# REC.net
KiCad netlist of a schematic drawn in Altium Designer
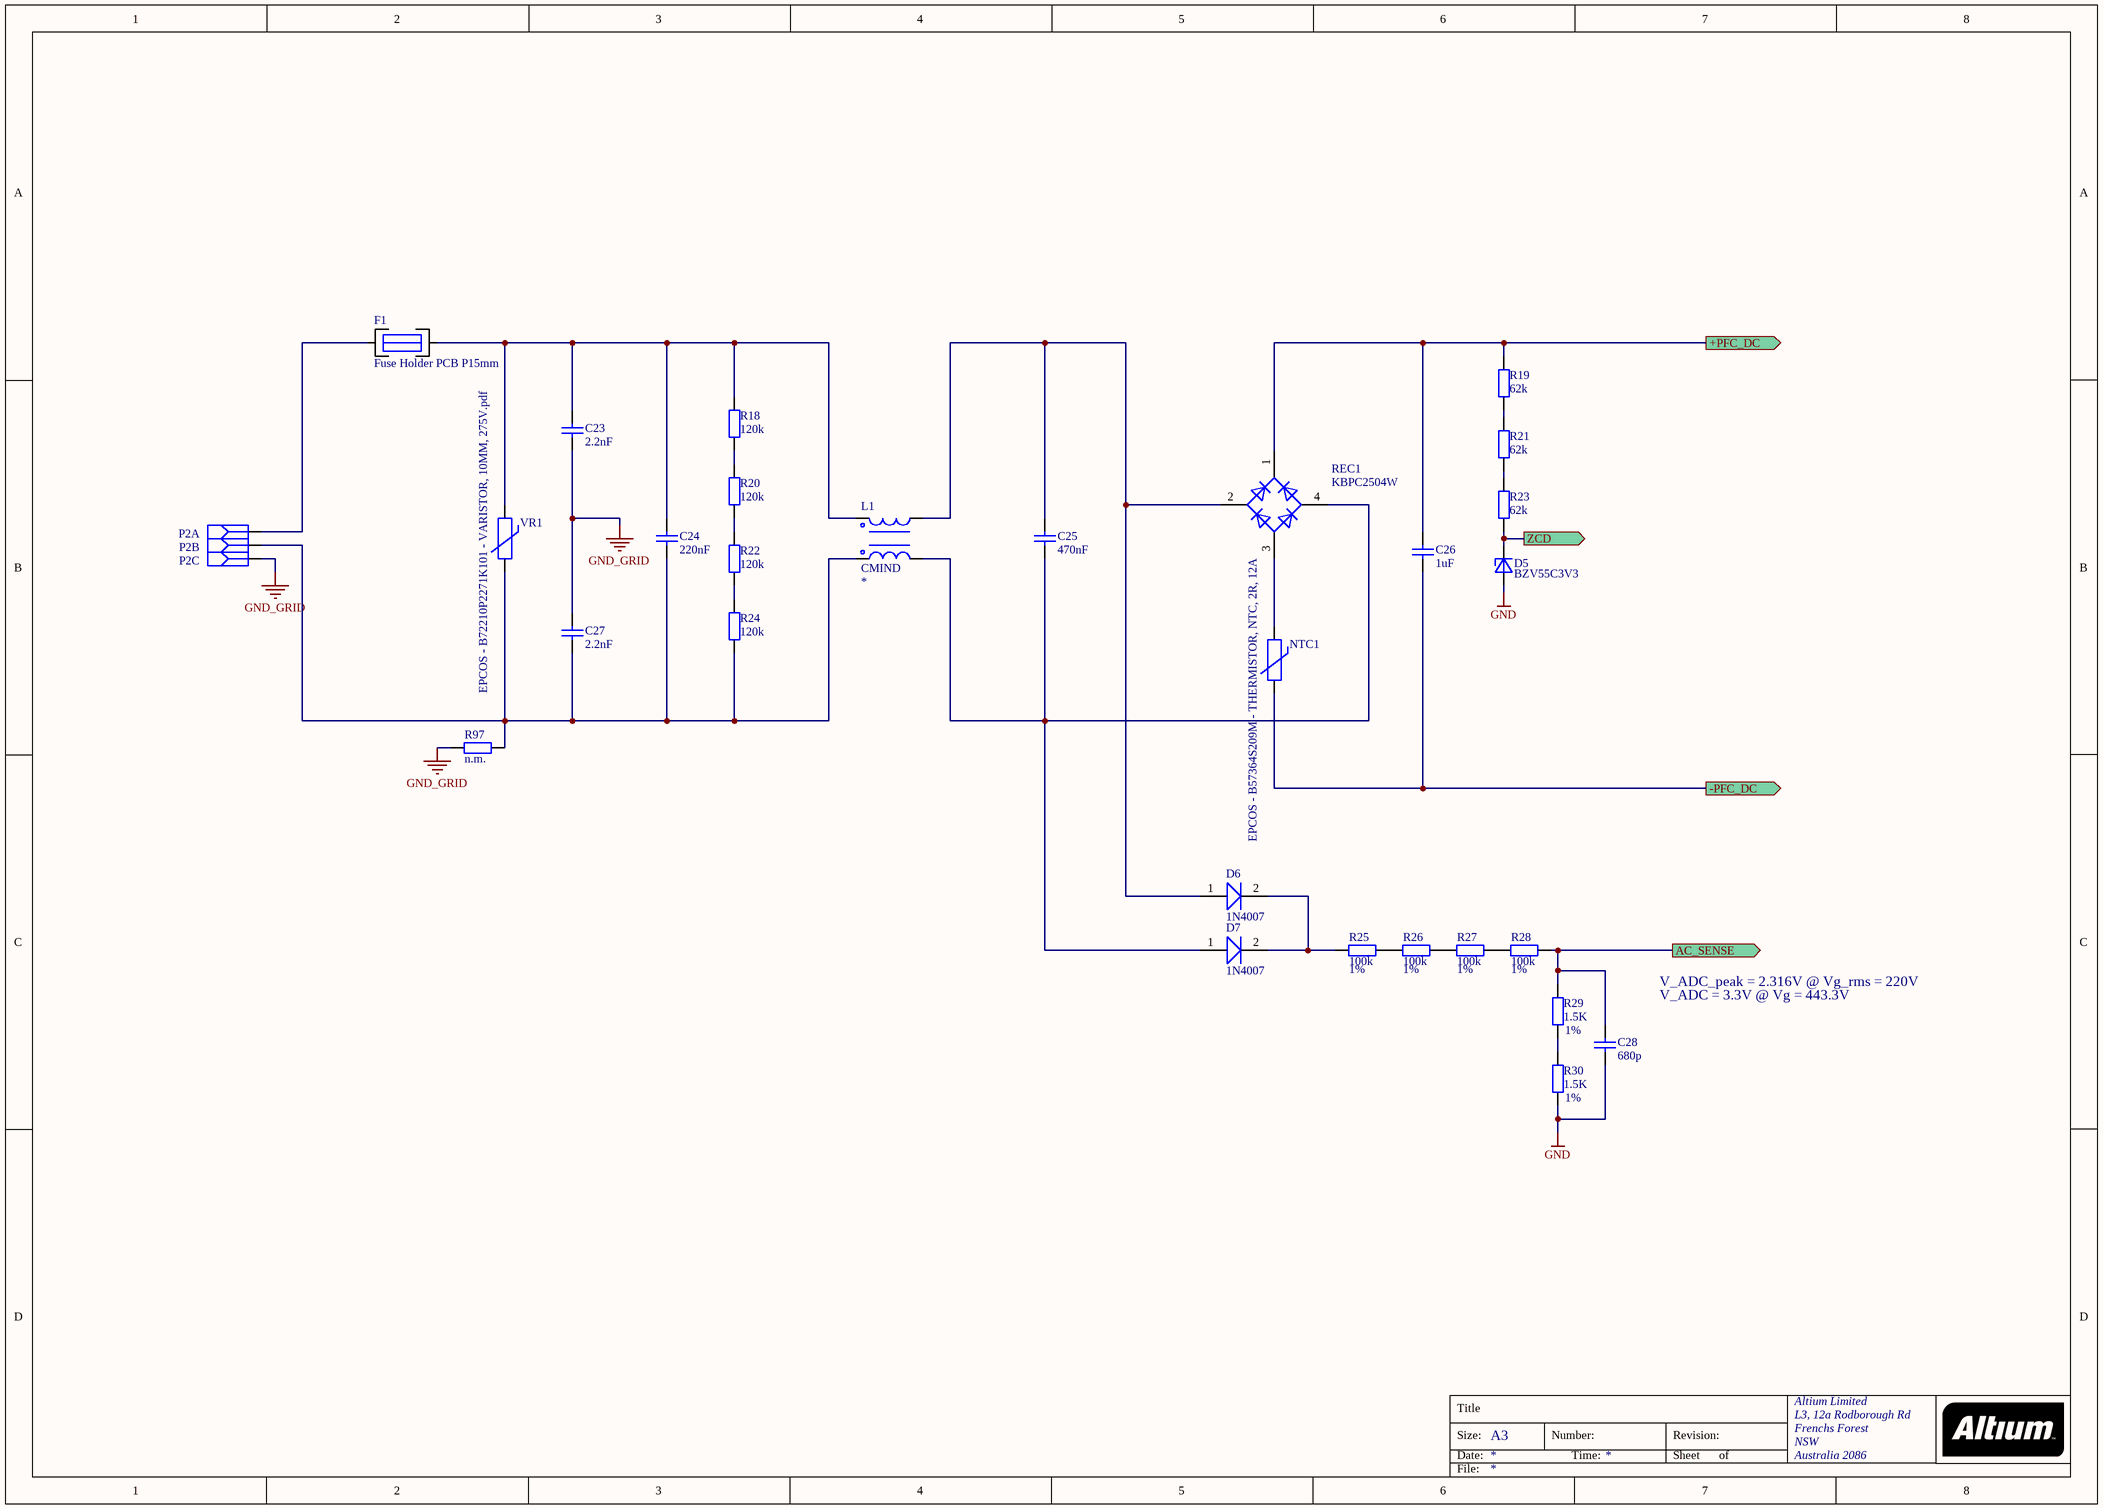
[diagram p0: REC.SchDoc]

(export (version "E")
  (design (tool "Eeschema 10.0.6"))
  (components
    (comp (ref "C23")
      (value "2.2nF")
      (footprint "RECT 18.0X7.0 RM15.0")
      (fields (field (name "Comment") "Cap"))
      (libsource (lib "Capacitors") (part "Cap"))
    )
    (comp (ref "C24")
      (value "220nF")
      (footprint "RECT 18.0X7.0 RM15.0")
      (fields (field (name "Comment") "Cap"))
      (libsource (lib "Capacitors") (part "Cap"))
    )
    (comp (ref "C25")
      (value "470nF")
      (footprint "RECT 18.0X7.0 RM15.0")
      (fields (field (name "Comment") "Cap"))
      (libsource (lib "Capacitors") (part "Cap"))
    )
    (comp (ref "C26")
      (value "1uF")
      (footprint "RECT 18.0X7.0 RM15.0")
      (fields (field (name "Comment") "Cap"))
      (libsource (lib "Capacitors") (part "Cap"))
    )
    (comp (ref "C27")
      (value "2.2nF")
      (footprint "RECT 18.0X7.0 RM15.0")
      (fields (field (name "Comment") "Cap"))
      (libsource (lib "Capacitors") (part "Cap"))
    )
    (comp (ref "C28")
      (value "680p")
      (footprint "1206_REFLOW")
      (fields (field (name "Comment") "Cap 1206"))
      (libsource (lib "Capacitors") (part "Cap 1206"))
    )
    (comp (ref "D5")
      (value "BZV55C3V3")
      (footprint "D_MINIMELF_BZV55C5V1(Primary)")
      (description "Zener Diode")
      (fields (field (name "Comment") "BZV55CXXX"))
      (libsource (lib "Zener") (part "BZV55CXXX"))
    )
    (comp (ref "D6")
      (value "1N4007")
      (footprint "AFL-W2/X1.8D")
      (description "1.0 Ampere General Purpose Rectifier")
      (libsource (lib "Diode") (part "1N4007"))
    )
    (comp (ref "D7")
      (value "1N4007")
      (footprint "AFL-W2/X1.8D")
      (description "1.0 Ampere General Purpose Rectifier")
      (libsource (lib "Diode") (part "1N4007"))
    )
    (comp (ref "F1")
      (value "Fuse Holder PCB P15mm")
      (footprint "Fuse Holder PCB P15mm")
      (libsource (lib "Fuse") (part "Fuse Holder PCB P15mm"))
    )
    (comp (ref "L1")
      (value "CMIND")
      (footprint "CommonModeChoke")
      (fields (field (name "ALTIUM_VALUE") "*"))
      (libsource (lib "Inductor") (part "CMIND"))
    )
    (comp (ref "NTC1")
      (value "EPCOS - B57364S209M - THERMISTOR, NTC, 2R, 12A")
      (footprint "VARISTOR_14")
      (fields (field (name "Comment") "Varristor"))
      (libsource (lib "Circuit Protection") (part "VAR"))
    )
    (comp (ref "P2")
      (value "MSTBA 2,5/ 3-G-5,08")
      (footprint "MSTBA2.5/3G-5.08")
      (description "Header, right angled, 12 A, 250 V, pitch 5.08 mm, No. of poles:4")
      (fields (field (name "MANUFACTURER") "Phoenix") (field (name "MFRR. PART NO.") "1757268"))
      (libsource (lib "Connector IDS") (part "MSTBA 2,5/ 3-G-5,08"))
    )
    (comp (ref "R18")
      (value "120k")
      (footprint "1206_REFLOW")
      (fields (field (name "Comment") "RES"))
      (libsource (lib "") (part "RES 1_1"))
    )
    (comp (ref "R19")
      (value "62k")
      (footprint "RA161004")
      (fields (field (name "TOLERANCE") "1%") (field (name "Comment") "RES"))
      (libsource (lib "") (part "RES 1_1"))
    )
    (comp (ref "R20")
      (value "120k")
      (footprint "1206_REFLOW")
      (fields (field (name "Comment") "RES"))
      (libsource (lib "") (part "RES 1_1"))
    )
    (comp (ref "R21")
      (value "62k")
      (footprint "RA161004")
      (fields (field (name "TOLERANCE") "1%") (field (name "Comment") "RES"))
      (libsource (lib "") (part "RES 1_1"))
    )
    (comp (ref "R22")
      (value "120k")
      (footprint "1206_REFLOW")
      (fields (field (name "Comment") "RES"))
      (libsource (lib "") (part "RES 1_1"))
    )
    (comp (ref "R23")
      (value "62k")
      (footprint "RA161004")
      (fields (field (name "TOLERANCE") "1%") (field (name "Comment") "RES"))
      (libsource (lib "") (part "RES 1_1"))
    )
    (comp (ref "R24")
      (value "120k")
      (footprint "1206_REFLOW")
      (fields (field (name "Comment") "RES"))
      (libsource (lib "") (part "RES 1_1"))
    )
    (comp (ref "R25")
      (value "100k")
      (footprint "RA161004")
      (fields (field (name "TOLERANCE") "1%") (field (name "Comment") "RES"))
      (libsource (lib "Resistor") (part "RES 1"))
    )
    (comp (ref "R26")
      (value "100k")
      (footprint "RA161004")
      (fields (field (name "TOLERANCE") "1%") (field (name "Comment") "RES"))
      (libsource (lib "Resistor") (part "RES 1"))
    )
    (comp (ref "R27")
      (value "100k")
      (footprint "RA161004")
      (fields (field (name "TOLERANCE") "1%") (field (name "Comment") "RES"))
      (libsource (lib "Resistor") (part "RES 1"))
    )
    (comp (ref "R28")
      (value "100k")
      (footprint "RA161004")
      (fields (field (name "TOLERANCE") "1%") (field (name "Comment") "RES"))
      (libsource (lib "Resistor") (part "RES 1"))
    )
    (comp (ref "R29")
      (value "1.5K")
      (footprint "RA161004")
      (fields (field (name "TOLERANCE") "1%") (field (name "Comment") "RES"))
      (libsource (lib "") (part "RES 1_1"))
    )
    (comp (ref "R30")
      (value "1.5K")
      (footprint "RA161004")
      (fields (field (name "TOLERANCE") "1%") (field (name "Comment") "RES"))
      (libsource (lib "") (part "RES 1_1"))
    )
    (comp (ref "R97")
      (value "n.m.")
      (footprint "1206_REFLOW")
      (fields (field (name "Comment") "RES"))
      (libsource (lib "Resistor") (part "RES 1"))
    )
    (comp (ref "REC1")
      (value "KBPC2504W")
      (footprint "KBPC2504W")
      (libsource (lib "Diode") (part "KBPC2504W"))
    )
    (comp (ref "VR1")
      (value "EPCOS - B72210P2271K101 - VARISTOR, 10MM, 275V.pdf")
      (footprint "VARISTOR_14")
      (fields (field (name "Comment") "Varristor"))
      (libsource (lib "Circuit Protection") (part "VAR"))
    )
  )
  (nets
    (net (code "1") (name "/+PFC_DC") (class "Default")
      (node (ref "C26") (pin "2") (pinfunction "2_2") (pintype "passive"))
      (node (ref "R19") (pin "1") (pinfunction "1_1") (pintype "passive"))
      (node (ref "REC1") (pin "1") (pinfunction "K_1") (pintype "passive"))
    )
    (net (code "2") (name "/-PFC_DC") (class "Default")
      (node (ref "C26") (pin "1") (pinfunction "1_1") (pintype "passive"))
      (node (ref "NTC1") (pin "2") (pinfunction "2_2") (pintype "passive"))
    )
    (net (code "3") (name "/AC_SENSE") (class "Default")
      (node (ref "C28") (pin "2") (pinfunction "2_2") (pintype "passive"))
      (node (ref "R28") (pin "2") (pinfunction "2_2") (pintype "passive"))
      (node (ref "R29") (pin "1") (pinfunction "1_1") (pintype "passive"))
    )
    (net (code "4") (name "/ZCD") (class "Default")
      (node (ref "D5") (pin "K") (pintype "passive"))
      (node (ref "R23") (pin "2") (pinfunction "2_2") (pintype "passive"))
    )
    (net (code "5") (name "GND") (class "Default")
      (node (ref "C28") (pin "1") (pinfunction "1_1") (pintype "passive"))
      (node (ref "D5") (pin "A") (pintype "passive"))
      (node (ref "R30") (pin "2") (pinfunction "2_2") (pintype "passive"))
    )
    (net (code "6") (name "GND_GRID") (class "Default")
      (node (ref "C23") (pin "1") (pinfunction "1_1") (pintype "passive"))
      (node (ref "C27") (pin "2") (pinfunction "2_2") (pintype "passive"))
      (node (ref "P2") (pin "3") (pinfunction "SIG_3") (pintype "passive"))
      (node (ref "R97") (pin "1") (pinfunction "1_1") (pintype "passive"))
    )
    (net (code "7") (name "Net-(C23-Pad2)") (class "Default")
      (node (ref "C23") (pin "2") (pinfunction "2_2") (pintype "passive"))
      (node (ref "C24") (pin "2") (pinfunction "2_2") (pintype "passive"))
      (node (ref "F1") (pin "2") (pinfunction "2_2") (pintype "passive"))
      (node (ref "L1") (pin "1") (pinfunction "1_1") (pintype "passive"))
      (node (ref "R18") (pin "1") (pinfunction "1_1") (pintype "passive"))
      (node (ref "VR1") (pin "1") (pinfunction "1_1") (pintype "passive"))
    )
    (net (code "8") (name "Net-(D6-A)") (class "Default")
      (node (ref "C25") (pin "2") (pinfunction "2_2") (pintype "passive"))
      (node (ref "D6") (pin "1") (pinfunction "A_1") (pintype "passive"))
      (node (ref "L1") (pin "2") (pinfunction "2_2") (pintype "passive"))
      (node (ref "REC1") (pin "2") (pinfunction "C_2") (pintype "passive"))
    )
    (net (code "9") (name "Net-(D6-K)") (class "Default")
      (node (ref "D6") (pin "2") (pinfunction "K_2") (pintype "passive"))
      (node (ref "D7") (pin "2") (pinfunction "K_2") (pintype "passive"))
      (node (ref "R25") (pin "1") (pinfunction "1_1") (pintype "passive"))
    )
    (net (code "10") (name "Net-(D7-A)") (class "Default")
      (node (ref "C25") (pin "1") (pinfunction "1_1") (pintype "passive"))
      (node (ref "D7") (pin "1") (pinfunction "A_1") (pintype "passive"))
      (node (ref "L1") (pin "4") (pinfunction "4_4") (pintype "passive"))
      (node (ref "REC1") (pin "4") (pinfunction "C_4") (pintype "passive"))
    )
    (net (code "11") (name "Net-(P2A-SIG)") (class "Default")
      (node (ref "F1") (pin "1") (pinfunction "1_1") (pintype "passive"))
      (node (ref "P2") (pin "1") (pinfunction "SIG_1") (pintype "passive"))
    )
    (net (code "12") (name "Net-(P2B-SIG)") (class "Default")
      (node (ref "C24") (pin "1") (pinfunction "1_1") (pintype "passive"))
      (node (ref "C27") (pin "1") (pinfunction "1_1") (pintype "passive"))
      (node (ref "L1") (pin "3") (pinfunction "3_3") (pintype "passive"))
      (node (ref "P2") (pin "2") (pinfunction "SIG_2") (pintype "passive"))
      (node (ref "R24") (pin "2") (pinfunction "2_2") (pintype "passive"))
      (node (ref "R97") (pin "2") (pinfunction "2_2") (pintype "passive"))
      (node (ref "VR1") (pin "2") (pinfunction "2_2") (pintype "passive"))
    )
    (net (code "13") (name "Net-(R18-Pad2)") (class "Default")
      (node (ref "R18") (pin "2") (pinfunction "2_2") (pintype "passive"))
      (node (ref "R20") (pin "1") (pinfunction "1_1") (pintype "passive"))
    )
    (net (code "14") (name "Net-(R19-Pad2)") (class "Default")
      (node (ref "R19") (pin "2") (pinfunction "2_2") (pintype "passive"))
      (node (ref "R21") (pin "1") (pinfunction "1_1") (pintype "passive"))
    )
    (net (code "15") (name "Net-(R20-Pad2)") (class "Default")
      (node (ref "R20") (pin "2") (pinfunction "2_2") (pintype "passive"))
      (node (ref "R22") (pin "1") (pinfunction "1_1") (pintype "passive"))
    )
    (net (code "16") (name "Net-(R21-Pad2)") (class "Default")
      (node (ref "R21") (pin "2") (pinfunction "2_2") (pintype "passive"))
      (node (ref "R23") (pin "1") (pinfunction "1_1") (pintype "passive"))
    )
    (net (code "17") (name "Net-(R22-Pad2)") (class "Default")
      (node (ref "R22") (pin "2") (pinfunction "2_2") (pintype "passive"))
      (node (ref "R24") (pin "1") (pinfunction "1_1") (pintype "passive"))
    )
    (net (code "18") (name "Net-(R25-Pad2)") (class "Default")
      (node (ref "R25") (pin "2") (pinfunction "2_2") (pintype "passive"))
      (node (ref "R26") (pin "1") (pinfunction "1_1") (pintype "passive"))
    )
    (net (code "19") (name "Net-(R26-Pad2)") (class "Default")
      (node (ref "R26") (pin "2") (pinfunction "2_2") (pintype "passive"))
      (node (ref "R27") (pin "1") (pinfunction "1_1") (pintype "passive"))
    )
    (net (code "20") (name "Net-(R27-Pad2)") (class "Default")
      (node (ref "R27") (pin "2") (pinfunction "2_2") (pintype "passive"))
      (node (ref "R28") (pin "1") (pinfunction "1_1") (pintype "passive"))
    )
    (net (code "21") (name "Net-(R29-Pad2)") (class "Default")
      (node (ref "R29") (pin "2") (pinfunction "2_2") (pintype "passive"))
      (node (ref "R30") (pin "1") (pinfunction "1_1") (pintype "passive"))
    )
    (net (code "22") (name "Net-(REC1-A)") (class "Default")
      (node (ref "NTC1") (pin "1") (pinfunction "1_1") (pintype "passive"))
      (node (ref "REC1") (pin "3") (pinfunction "A_3") (pintype "passive"))
    )
  )
)
